# Audio_Controller.net
KiCad netlist of a schematic drawn in Altium Designer
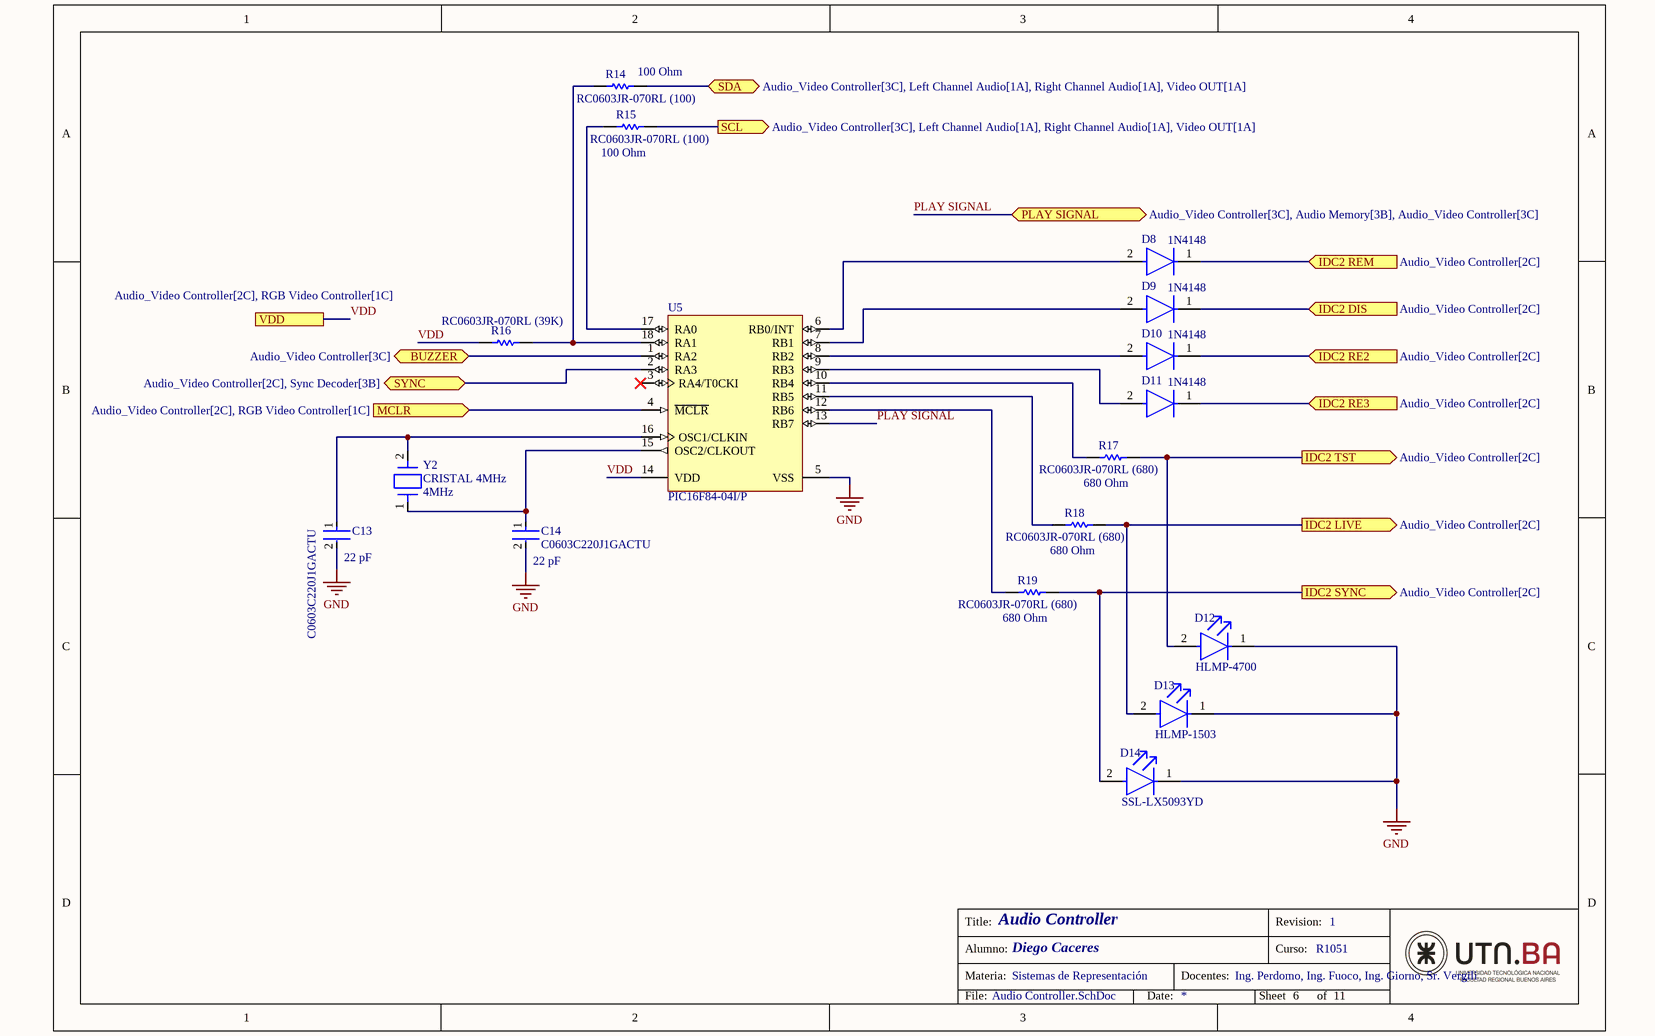
[diagram p0: Audio Controller.SchDoc]

(export (version "E")
  (design (tool "Eeschema 10.0.6"))
  (components
    (comp (ref "C13")
      (value "C0603C220J1GACTU")
      (footprint "FP-C0603C-CF-MFG")
      (description "CAP CER 22PF 100V 5% NP0 0603")
      (fields
        (field (name "CAPACITANCE") "22 pF")
        (field (name "MANUFACTURER") "KEMET")
        (field (name "TOLERANCE") "0.05")
      )
      (libsource (lib "Altium Content Vault") (part "b4654b650e69147ec39a6b967a45e02"))
    )
    (comp (ref "C14")
      (value "C0603C220J1GACTU")
      (footprint "FP-C0603C-CF-MFG")
      (description "CAP CER 22PF 100V 5% NP0 0603")
      (fields
        (field (name "ALTIUM_VALUE") "22 pF")
        (field (name "MANUFACTURER") "KEMET")
        (field (name "TOLERANCE") "0.05")
      )
      (libsource (lib "Altium Content Vault") (part "b4654b650e69147ec39a6b967a45e02"))
    )
    (comp (ref "D8")
      (value "1N4148")
      (footprint "FP-017AG-MFG")
      (description "DIODE GEN PURP 100V 200MA DO35")
      (fields (field (name "VOLTAGE") "100V"))
      (libsource (lib "Altium Content Vault") (part "d7152d700b627762746794eb795d46e"))
    )
    (comp (ref "D9")
      (value "1N4148")
      (footprint "FP-017AG-MFG")
      (description "DIODE GEN PURP 100V 200MA DO35")
      (fields (field (name "VOLTAGE") "100V"))
      (libsource (lib "Altium Content Vault") (part "d7152d700b627762746794eb795d46e"))
    )
    (comp (ref "D10")
      (value "1N4148")
      (footprint "FP-017AG-MFG")
      (description "DIODE GEN PURP 100V 200MA DO35")
      (fields (field (name "VOLTAGE") "100V"))
      (libsource (lib "Altium Content Vault") (part "d7152d700b627762746794eb795d46e"))
    )
    (comp (ref "D11")
      (value "1N4148")
      (footprint "FP-017AG-MFG")
      (description "DIODE GEN PURP 100V 200MA DO35")
      (fields (field (name "VOLTAGE") "100V"))
      (libsource (lib "Altium Content Vault") (part "d7152d700b627762746794eb795d46e"))
    )
    (comp (ref "D12")
      (value "HLMP-4700")
      (footprint "FP-HLMP-4700-MFG")
      (description "LED RED DIFFUSED T-1 3/4 T/H")
      (fields
        (field (name "OCTOPART") "https://octopart.com/hlmp-4700-broadcom-71130526")
        (field (name "MANUFACTURER") "Broadcom")
      )
      (libsource (lib "Altium Content Vault") (part "8706943c75ba83719d021d2fdc84c58"))
    )
    (comp (ref "D13")
      (value "HLMP-1503")
      (footprint "FP-HLMP-1503-MFG")
      (description "LED GREEN DIFFUSED T-1 T/H")
      (fields
        (field (name "MANUFACTURER") "Broadcom")
        (field (name "OCTOPART") "https://octopart.com/hlmp-1503-broadcom-71130371")
      )
      (libsource (lib "Altium Content Vault") (part "8706943c75ba83719d021d2fdc84c58"))
    )
    (comp (ref "D14")
      (value "SSL-LX5093YD")
      (footprint "FP-SSL-LX5093YD-MFG")
      (description "LED YELLOW DIFFUSED T-1 3/4 T/H")
      (libsource (lib "Altium Content Vault") (part "8706943c75ba83719d021d2fdc84c58"))
    )
    (comp (ref "R14")
      (value "RC0603JR-070RL (100)")
      (footprint "RESC1608X55X25ML10T15")
      (description "Chip Resistor, 0 Ohm, +/- 5%, 0.1 W, -55 to 155 degC, 0603 (1608 Metric), RoHS, Tape and Reel")
      (fields
        (field (name "TOLERANCE") "5%")
        (field (name "RESISTANCE") "100 Ohm")
        (field (name "MANUFACTURER") "Yageo")
      )
      (libsource (lib "Altium Content Vault") (part "RES-2"))
    )
    (comp (ref "R15")
      (value "RC0603JR-070RL (100)")
      (footprint "RESC1608X55X25ML10T15")
      (description "Chip Resistor, 0 Ohm, +/- 5%, 0.1 W, -55 to 155 degC, 0603 (1608 Metric), RoHS, Tape and Reel")
      (fields
        (field (name "TOLERANCE") "5%")
        (field (name "RESISTANCE") "100 Ohm")
        (field (name "MANUFACTURER") "Yageo")
      )
      (libsource (lib "Altium Content Vault") (part "RES-2"))
    )
    (comp (ref "R16")
      (value "RC0603JR-070RL (39K)")
      (footprint "RESC1608X55X25ML10T15")
      (description "Chip Resistor, 0 Ohm, +/- 5%, 0.1 W, -55 to 155 degC, 0603 (1608 Metric), RoHS, Tape and Reel")
      (fields (field (name "TOLERANCE") "5%") (field (name "MANUFACTURER") "Yageo"))
      (libsource (lib "Altium Content Vault") (part "RES-2"))
    )
    (comp (ref "R17")
      (value "RC0603JR-070RL (680)")
      (footprint "RESC1608X55X25ML10T15")
      (description "Chip Resistor, 0 Ohm, +/- 5%, 0.1 W, -55 to 155 degC, 0603 (1608 Metric), RoHS, Tape and Reel")
      (fields
        (field (name "TOLERANCE") "5%")
        (field (name "RESISTANCE") "680 Ohm")
        (field (name "MANUFACTURER") "Yageo")
      )
      (libsource (lib "Altium Content Vault") (part "RES-2"))
    )
    (comp (ref "R18")
      (value "RC0603JR-070RL (680)")
      (footprint "RESC1608X55X25ML10T15")
      (description "Chip Resistor, 0 Ohm, +/- 5%, 0.1 W, -55 to 155 degC, 0603 (1608 Metric), RoHS, Tape and Reel")
      (fields
        (field (name "TOLERANCE") "5%")
        (field (name "RESISTANCE") "680 Ohm")
        (field (name "MANUFACTURER") "Yageo")
      )
      (libsource (lib "Altium Content Vault") (part "RES-2"))
    )
    (comp (ref "R19")
      (value "RC0603JR-070RL (680)")
      (footprint "RESC1608X55X25ML10T15")
      (description "Chip Resistor, 0 Ohm, +/- 5%, 0.1 W, -55 to 155 degC, 0603 (1608 Metric), RoHS, Tape and Reel")
      (fields
        (field (name "TOLERANCE") "5%")
        (field (name "RESISTANCE") "680 Ohm")
        (field (name "MANUFACTURER") "Yageo")
      )
      (libsource (lib "Altium Content Vault") (part "RES-2"))
    )
    (comp (ref "U5")
      (value "PIC16F84-04I/P")
      (footprint "MCHP-PDIP-P18")
      (description "Flash / EEPROM 8-Bit Microcontroller, 4 MHz, 13 I/O, -40 to 85 degC, 18-pin PDIP (P18), Tube")
      (fields (field (name "MANUFACTURER") "Microchip"))
      (libsource (lib "Altium Content Vault") (part "MCHP-PIC16F83_84-18"))
    )
    (comp (ref "Y2")
      (value "CRISTAL 4MHz")
      (footprint "HC-49/US_SMD_CRISTAL 4MHz_DCACERES")
      (description "Cristal SMD 4.00MHz")
      (fields
        (field (name "FREQUENCY") "4MHz")
        (field (name "PARTNUMBER") "ABLS-4.000MHZ-K4T")
        (field (name "MANUFACTURER") "Abracon")
      )
      (libsource (lib "PF_Schlib") (part "Cristal_4MHz_Caceres"))
    )
  )
  (nets
    (net (code "1") (name "/BUZZER") (class "Default")
      (node (ref "U5") (pin "1") (pinfunction "RA2_1") (pintype "bidirectional"))
    )
    (net (code "2") (name "/IDC2 DIS") (class "Default")
      (node (ref "D9") (pin "1") (pinfunction "C_1") (pintype "passive"))
    )
    (net (code "3") (name "/IDC2 LIVE") (class "Default")
      (node (ref "D13") (pin "2") (pinfunction "A_2") (pintype "passive"))
      (node (ref "R18") (pin "1") (pinfunction "1_1") (pintype "passive"))
    )
    (net (code "4") (name "/IDC2 RE2") (class "Default")
      (node (ref "D10") (pin "1") (pinfunction "C_1") (pintype "passive"))
    )
    (net (code "5") (name "/IDC2 RE3") (class "Default")
      (node (ref "D11") (pin "1") (pinfunction "C_1") (pintype "passive"))
    )
    (net (code "6") (name "/IDC2 REM") (class "Default")
      (node (ref "D8") (pin "1") (pinfunction "C_1") (pintype "passive"))
    )
    (net (code "7") (name "/IDC2 SYNC") (class "Default")
      (node (ref "D14") (pin "2") (pinfunction "A_2") (pintype "passive"))
      (node (ref "R19") (pin "1") (pinfunction "1_1") (pintype "passive"))
    )
    (net (code "8") (name "/IDC2 TST") (class "Default")
      (node (ref "D12") (pin "2") (pinfunction "A_2") (pintype "passive"))
      (node (ref "R17") (pin "1") (pinfunction "1_1") (pintype "passive"))
    )
    (net (code "9") (name "/MCLR") (class "Default")
      (node (ref "U5") (pin "4") (pinfunction "~{MCLR}_4") (pintype "input"))
    )
    (net (code "10") (name "/PLAY SIGNAL") (class "Default")
      (node (ref "U5") (pin "13") (pinfunction "RB7_13") (pintype "bidirectional"))
    )
    (net (code "11") (name "/SCL") (class "Default")
      (node (ref "R15") (pin "1") (pinfunction "1_1") (pintype "passive"))
    )
    (net (code "12") (name "/SDA") (class "Default")
      (node (ref "R14") (pin "1") (pinfunction "1_1") (pintype "passive"))
    )
    (net (code "13") (name "/SYNC") (class "Default")
      (node (ref "U5") (pin "2") (pinfunction "RA3_2") (pintype "bidirectional"))
    )
    (net (code "14") (name "/VDD") (class "Default")
      (node (ref "R16") (pin "2") (pinfunction "2_2") (pintype "passive"))
      (node (ref "U5") (pin "14") (pinfunction "VDD_14") (pintype "power_in"))
    )
    (net (code "15") (name "GND") (class "Default")
      (node (ref "C13") (pin "2") (pinfunction "2_2") (pintype "passive"))
      (node (ref "C14") (pin "2") (pinfunction "2_2") (pintype "passive"))
      (node (ref "D12") (pin "1") (pinfunction "C_1") (pintype "passive"))
      (node (ref "D13") (pin "1") (pinfunction "C_1") (pintype "passive"))
      (node (ref "D14") (pin "1") (pinfunction "C_1") (pintype "passive"))
      (node (ref "U5") (pin "5") (pinfunction "VSS_5") (pintype "power_in"))
    )
    (net (code "16") (name "Net-(D8-A)") (class "Default")
      (node (ref "D8") (pin "2") (pinfunction "A_2") (pintype "passive"))
      (node (ref "U5") (pin "6") (pinfunction "RB0/INT_6") (pintype "bidirectional"))
    )
    (net (code "17") (name "Net-(D9-A)") (class "Default")
      (node (ref "D9") (pin "2") (pinfunction "A_2") (pintype "passive"))
      (node (ref "U5") (pin "7") (pinfunction "RB1_7") (pintype "bidirectional"))
    )
    (net (code "18") (name "Net-(D10-A)") (class "Default")
      (node (ref "D10") (pin "2") (pinfunction "A_2") (pintype "passive"))
      (node (ref "U5") (pin "8") (pinfunction "RB2_8") (pintype "bidirectional"))
    )
    (net (code "19") (name "Net-(D11-A)") (class "Default")
      (node (ref "D11") (pin "2") (pinfunction "A_2") (pintype "passive"))
      (node (ref "U5") (pin "9") (pinfunction "RB3_9") (pintype "bidirectional"))
    )
    (net (code "20") (name "Net-(U5-OSC1{slash}CLKIN)") (class "Default")
      (node (ref "C13") (pin "1") (pinfunction "1_1") (pintype "passive"))
      (node (ref "U5") (pin "16") (pinfunction "OSC1/CLKIN_16") (pintype "input"))
      (node (ref "Y2") (pin "2") (pinfunction "2_2") (pintype "passive"))
    )
    (net (code "21") (name "Net-(U5-OSC2{slash}CLKOUT)") (class "Default")
      (node (ref "C14") (pin "1") (pinfunction "1_1") (pintype "passive"))
      (node (ref "U5") (pin "15") (pinfunction "OSC2/CLKOUT_15") (pintype "output"))
      (node (ref "Y2") (pin "1") (pinfunction "1_1") (pintype "passive"))
    )
    (net (code "22") (name "Net-(U5-RA0)") (class "Default")
      (node (ref "R15") (pin "2") (pinfunction "2_2") (pintype "passive"))
      (node (ref "U5") (pin "17") (pinfunction "RA0_17") (pintype "bidirectional"))
    )
    (net (code "23") (name "Net-(U5-RA1)") (class "Default")
      (node (ref "R14") (pin "2") (pinfunction "2_2") (pintype "passive"))
      (node (ref "R16") (pin "1") (pinfunction "1_1") (pintype "passive"))
      (node (ref "U5") (pin "18") (pinfunction "RA1_18") (pintype "bidirectional"))
    )
    (net (code "24") (name "Net-(U5-RB4)") (class "Default")
      (node (ref "R17") (pin "2") (pinfunction "2_2") (pintype "passive"))
      (node (ref "U5") (pin "10") (pinfunction "RB4_10") (pintype "bidirectional"))
    )
    (net (code "25") (name "Net-(U5-RB5)") (class "Default")
      (node (ref "R18") (pin "2") (pinfunction "2_2") (pintype "passive"))
      (node (ref "U5") (pin "11") (pinfunction "RB5_11") (pintype "bidirectional"))
    )
    (net (code "26") (name "Net-(U5-RB6)") (class "Default")
      (node (ref "R19") (pin "2") (pinfunction "2_2") (pintype "passive"))
      (node (ref "U5") (pin "12") (pinfunction "RB6_12") (pintype "bidirectional"))
    )
    (net (code "27") (name "unconnected-(U5-RA4{slash}T0CKI-Pad3)") (class "Default")
      (node (ref "U5") (pin "3") (pinfunction "RA4/T0CKI_3") (pintype "bidirectional+no_connect"))
    )
  )
)
